# Presure_Sensor_Breakout.net
KiCad netlist of a schematic drawn in EAGLE
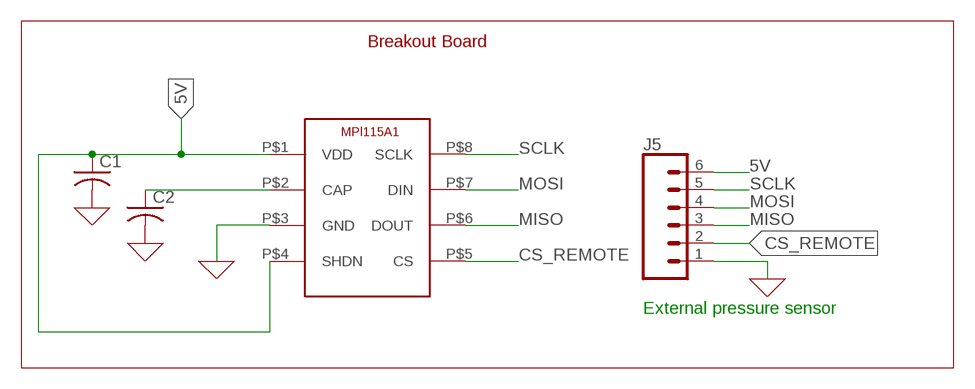
[diagram p0: schematic, sheet 1]

(export (version "E")
  (design (tool "Eeschema 10.0.6"))
  (components
    (comp (ref "C1")
      (value "C-USC0805")
      (footprint "eagle-import:C0805")
      (libsource (lib "eagle-import") (part "C-USC0805"))
    )
    (comp (ref "C2")
      (value "C-USC0805")
      (footprint "eagle-import:C0805")
      (libsource (lib "eagle-import") (part "C-USC0805"))
    )
    (comp (ref "J5")
      (value "CONN_06LOCK_LONGPADS")
      (footprint "eagle-import:1X06_LOCK_LONGPADS")
      (libsource (lib "eagle-import") (part "CONN_06LOCK_LONGPADS"))
    )
    (comp (ref "U$1")
      (value "MPL115A1")
      (footprint "eagle-import:MPL115A1")
      (libsource (lib "eagle-import") (part "MPL115A1"))
    )
  )
  (nets
    (net (code "1") (name "/MISO") (class "Default")
      (node (ref "J5") (pin "3") (pinfunction "3_3") (pintype "passive"))
      (node (ref "U$1") (pin "P$6") (pinfunction "DOUT_P$6") (pintype "bidirectional"))
    )
    (net (code "2") (name "/MOSI") (class "Default")
      (node (ref "J5") (pin "4") (pinfunction "4_4") (pintype "passive"))
      (node (ref "U$1") (pin "P$7") (pinfunction "DIN_P$7") (pintype "bidirectional"))
    )
    (net (code "3") (name "/SCLK") (class "Default")
      (node (ref "J5") (pin "5") (pinfunction "5_5") (pintype "passive"))
      (node (ref "U$1") (pin "P$8") (pinfunction "SCLK_P$8") (pintype "bidirectional"))
    )
    (net (code "4") (name "5V") (class "Default")
      (node (ref "C1") (pin "1") (pinfunction "1_1") (pintype "passive"))
      (node (ref "J5") (pin "6") (pinfunction "6_6") (pintype "passive"))
      (node (ref "U$1") (pin "P$1") (pinfunction "VDD_P$1") (pintype "bidirectional"))
      (node (ref "U$1") (pin "P$4") (pinfunction "SHDN_P$4") (pintype "bidirectional"))
    )
    (net (code "5") (name "CS_REMOTE") (class "Default")
      (node (ref "J5") (pin "2") (pinfunction "2_2") (pintype "passive"))
      (node (ref "U$1") (pin "P$5") (pinfunction "CS_P$5") (pintype "bidirectional"))
    )
    (net (code "6") (name "GND") (class "Default")
      (node (ref "C1") (pin "2") (pinfunction "2_2") (pintype "passive"))
      (node (ref "C2") (pin "2") (pinfunction "2_2") (pintype "passive"))
      (node (ref "J5") (pin "1") (pinfunction "1_1") (pintype "passive"))
      (node (ref "U$1") (pin "P$3") (pinfunction "GND_P$3") (pintype "bidirectional"))
    )
    (net (code "7") (name "Net-(U$1-CAP)") (class "Default")
      (node (ref "C2") (pin "1") (pinfunction "1_1") (pintype "passive"))
      (node (ref "U$1") (pin "P$2") (pinfunction "CAP_P$2") (pintype "bidirectional"))
    )
  )
)
